# moire_v2_1.net
KiCad netlist of a schematic drawn in EAGLE
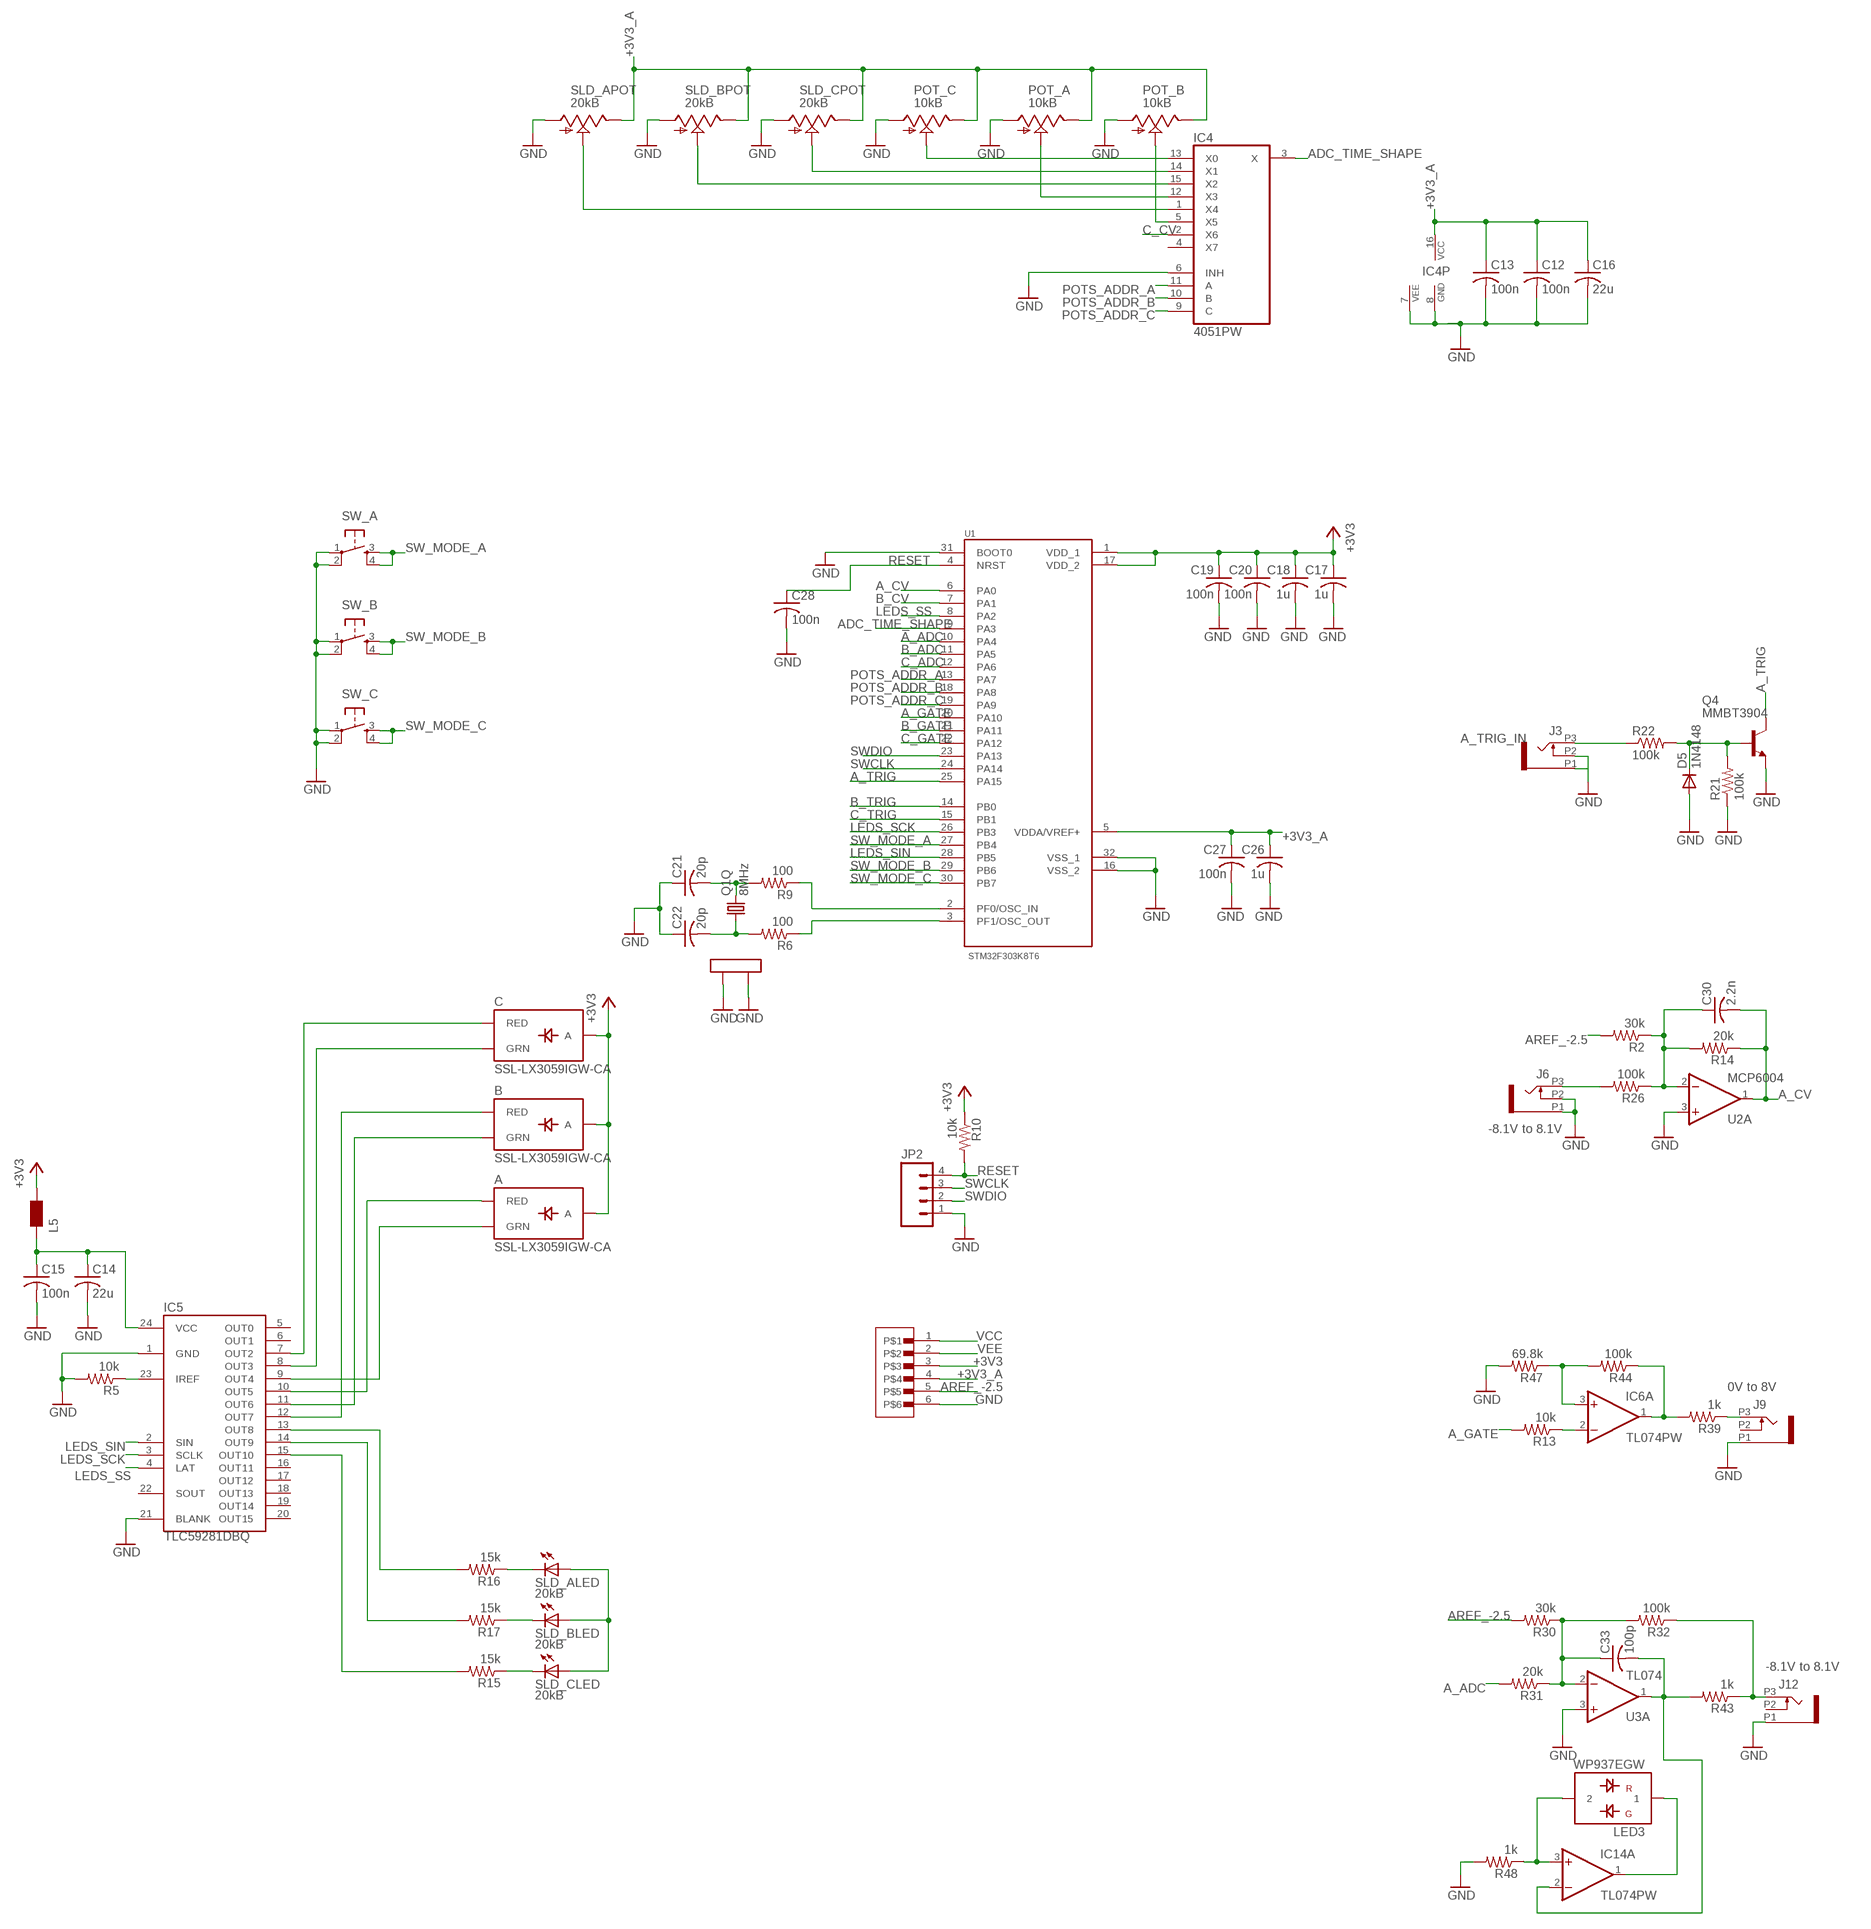
[diagram p0: schematic, sheet 1, part 1 of 2]
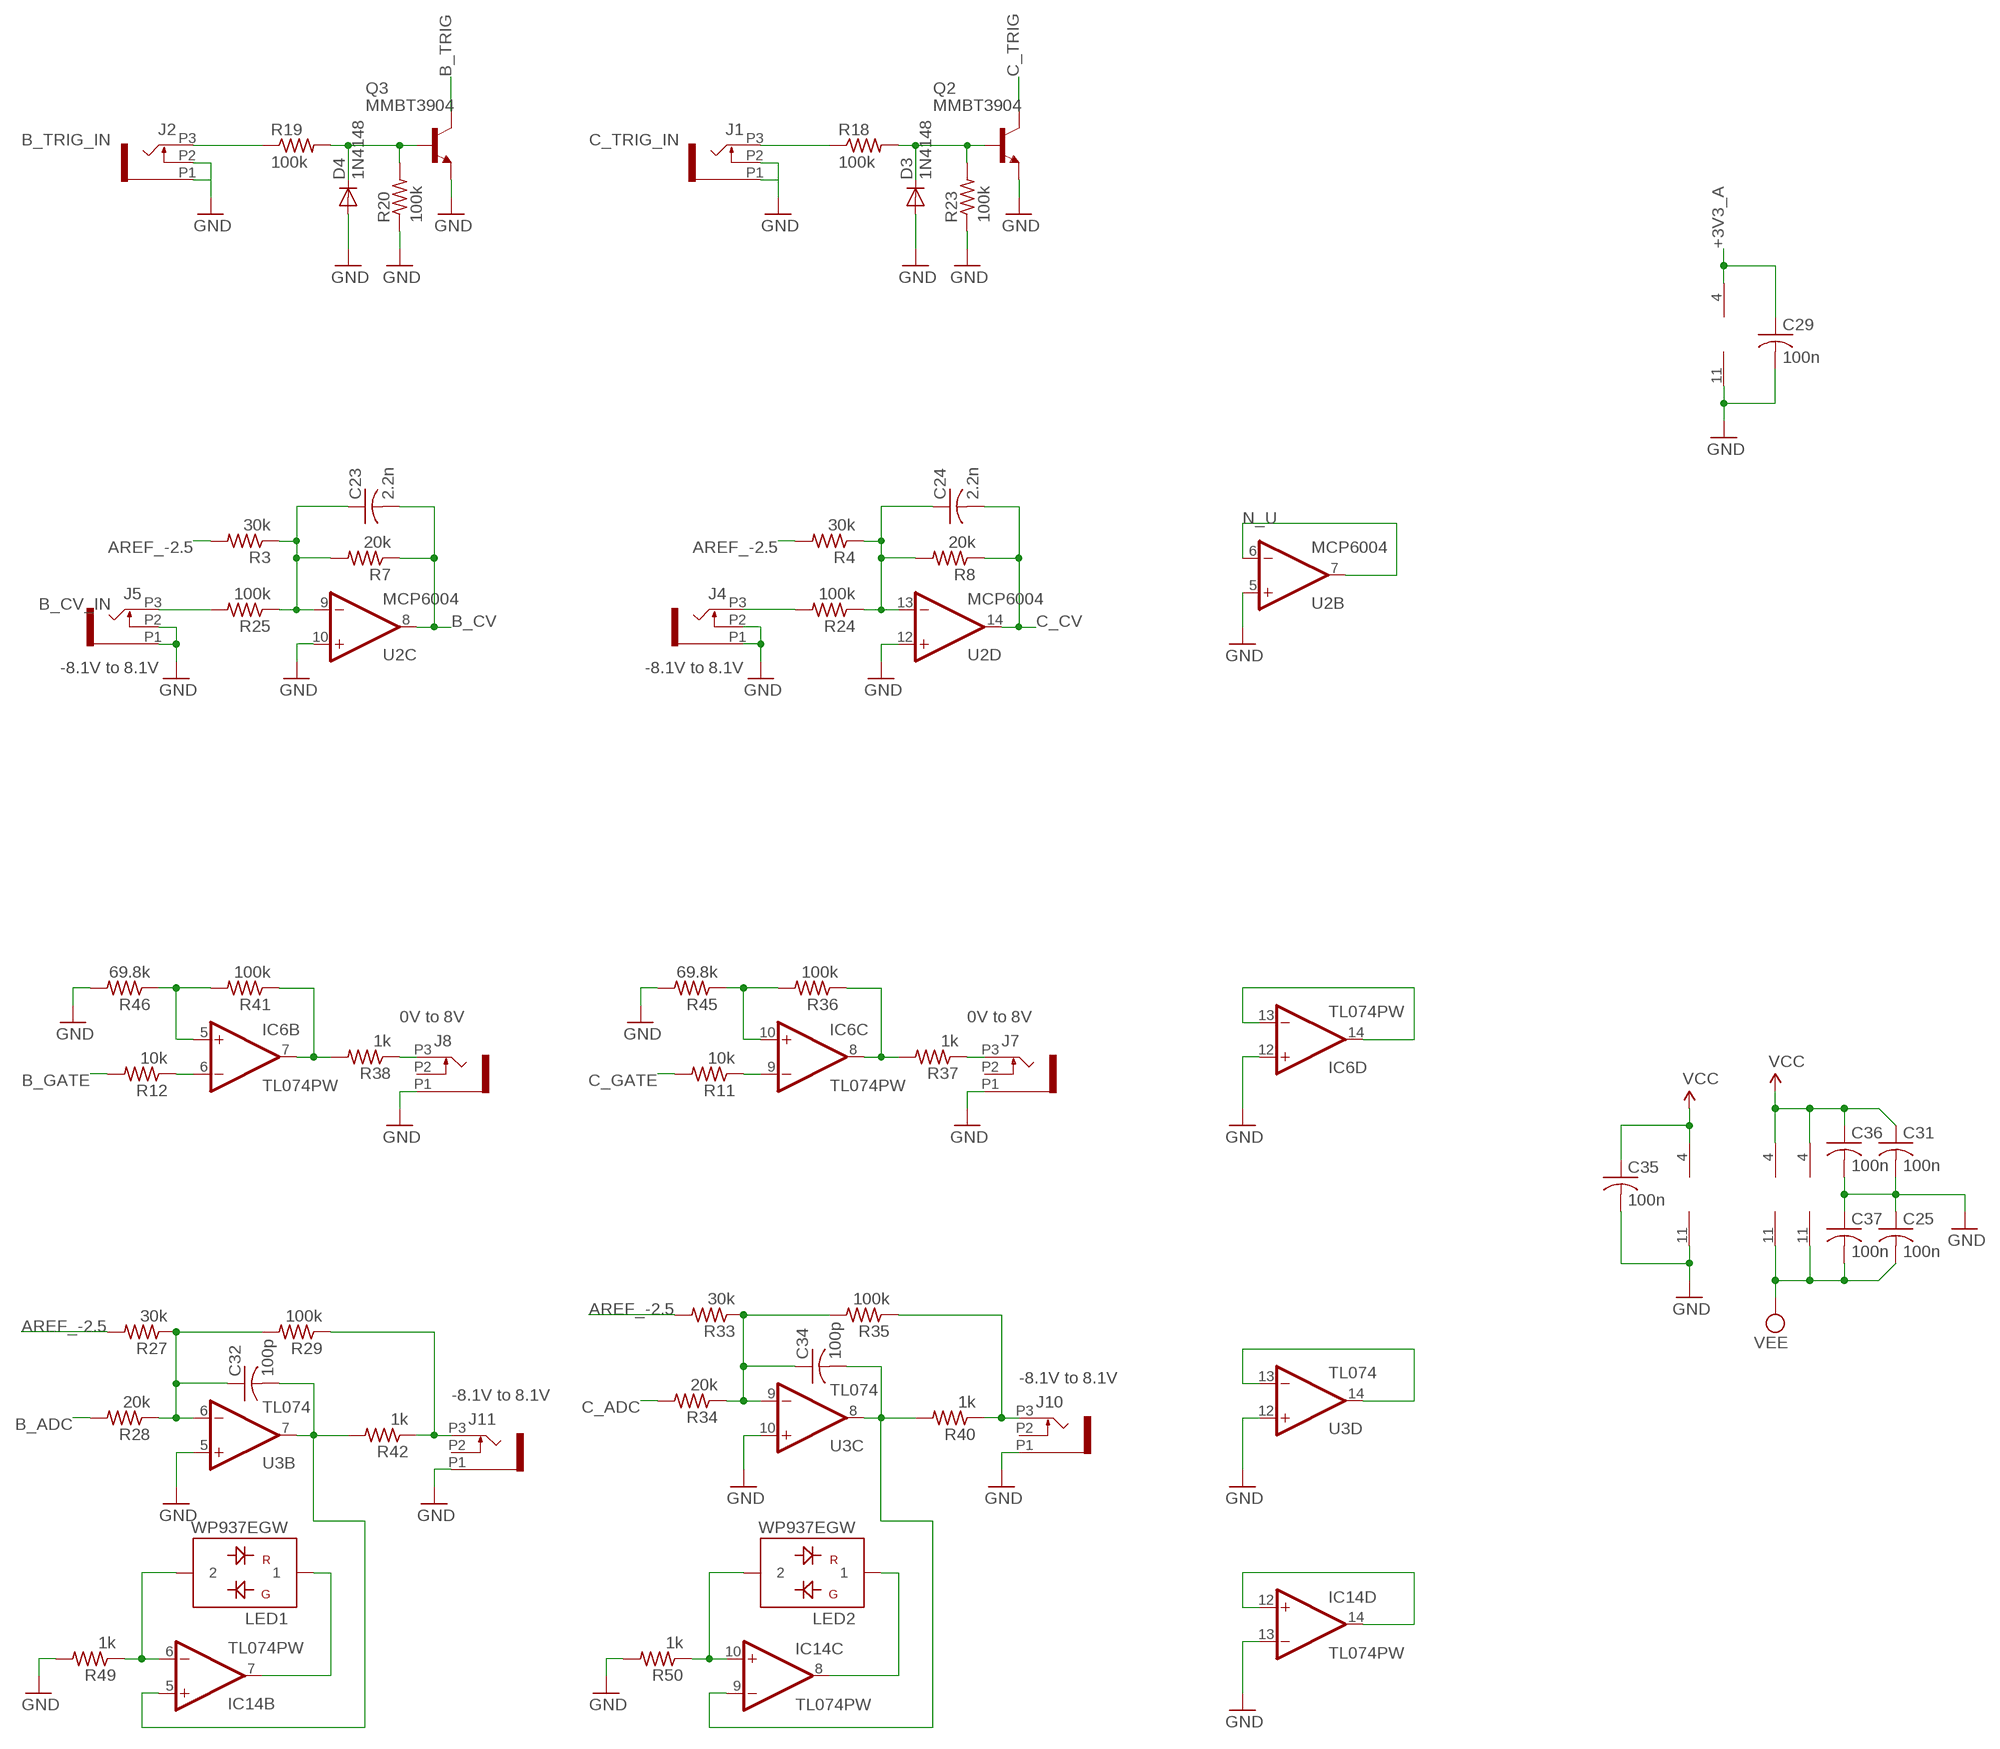
[diagram p1: schematic, sheet 1, part 2 of 2]
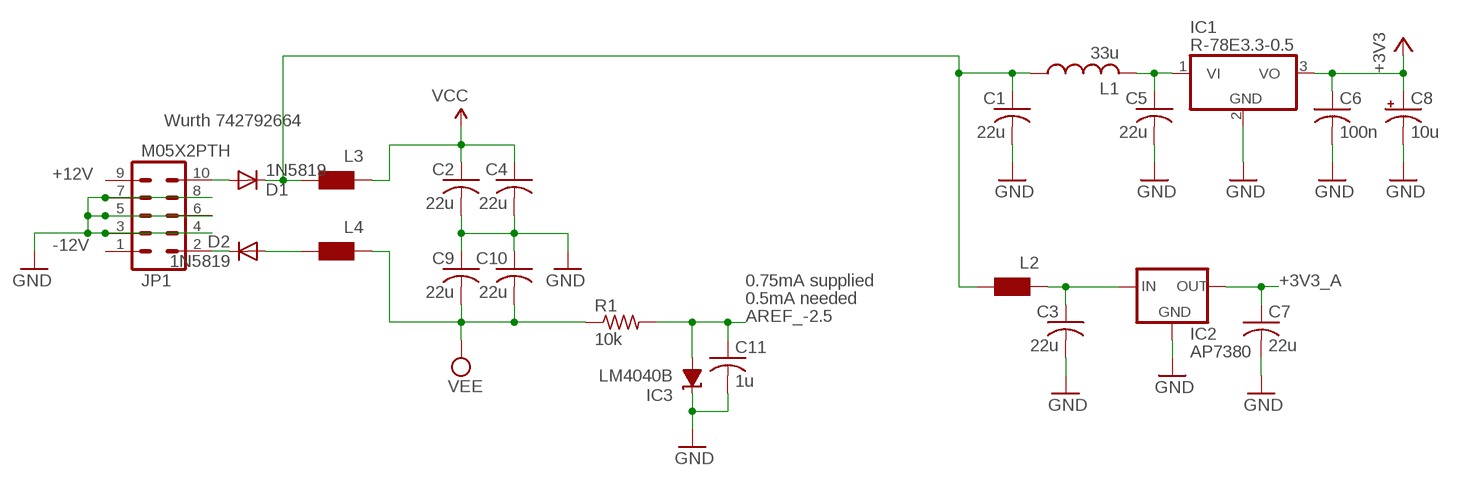
[diagram p2: schematic, sheet 2]

(export (version "E")
  (design (tool "Eeschema 10.0.6"))
  (components
    (comp (ref "C1")
      (value "22u")
      (footprint "eagle-import:RCL_C1206")
      (libsource (lib "eagle-import") (part "RCL_C-USC1206"))
    )
    (comp (ref "C2")
      (value "22u")
      (footprint "eagle-import:RCL_C1206")
      (libsource (lib "eagle-import") (part "RCL_C-USC1206"))
    )
    (comp (ref "C3")
      (value "22u")
      (footprint "eagle-import:RCL_C1206")
      (libsource (lib "eagle-import") (part "RCL_C-USC1206"))
    )
    (comp (ref "C4")
      (value "22u")
      (footprint "eagle-import:RCL_C1206")
      (libsource (lib "eagle-import") (part "RCL_C-USC1206"))
    )
    (comp (ref "C5")
      (value "22u")
      (footprint "eagle-import:RCL_C1206")
      (libsource (lib "eagle-import") (part "RCL_C-USC1206"))
    )
    (comp (ref "C6")
      (value "100n")
      (footprint "eagle-import:RCL_C0603")
      (libsource (lib "eagle-import") (part "RCL_C-USC0603"))
    )
    (comp (ref "C7")
      (value "22u")
      (footprint "eagle-import:RCL_C1206")
      (libsource (lib "eagle-import") (part "RCL_C-USC1206"))
    )
    (comp (ref "C8")
      (value "10u")
      (footprint "eagle-import:RCL_PANASONIC_A")
      (libsource (lib "eagle-import") (part "RCL_CPOL-USA"))
    )
    (comp (ref "C9")
      (value "22u")
      (footprint "eagle-import:RCL_C1206")
      (libsource (lib "eagle-import") (part "RCL_C-USC1206"))
    )
    (comp (ref "C10")
      (value "22u")
      (footprint "eagle-import:RCL_C1206")
      (libsource (lib "eagle-import") (part "RCL_C-USC1206"))
    )
    (comp (ref "C11")
      (value "1u")
      (footprint "eagle-import:RCL_C0603")
      (libsource (lib "eagle-import") (part "RCL_C-USC0603"))
    )
    (comp (ref "D1")
      (value "1N5819")
      (footprint "eagle-import:DIODE_SOD123")
      (libsource (lib "eagle-import") (part "DIODE_DIODE-SOD123"))
    )
    (comp (ref "D2")
      (value "1N5819")
      (footprint "eagle-import:DIODE_SOD123")
      (libsource (lib "eagle-import") (part "DIODE_DIODE-SOD123"))
    )
    (comp (ref "IC1")
      (value "R-78E3.3-0.5")
      (footprint "eagle-import:WE78")
      (libsource (lib "eagle-import") (part "WE173950378"))
    )
    (comp (ref "IC2")
      (value "AP7380")
      (footprint "eagle-import:SOT89")
      (libsource (lib "eagle-import") (part "AP7380"))
    )
    (comp (ref "IC3")
      (value "LM4040B")
      (footprint "eagle-import:DBZ_R-PDSO-G3")
      (libsource (lib "eagle-import") (part "LM4041DBZB12"))
    )
    (comp (ref "JP1")
      (value "M05X2PTH")
      (footprint "eagle-import:2X5-PTH")
      (libsource (lib "eagle-import") (part "M05X2PTH"))
    )
    (comp (ref "L1")
      (value "33u")
      (footprint "eagle-import:L2012C")
      (libsource (lib "eagle-import") (part "L-USL2012C"))
    )
    (comp (ref "L2")
      (value "WE-CBF_0603")
      (footprint "eagle-import:0603")
      (libsource (lib "eagle-import") (part "WE-CBF_0603"))
    )
    (comp (ref "L3")
      (value "WE-CBF_0603")
      (footprint "eagle-import:0603")
      (libsource (lib "eagle-import") (part "WE-CBF_0603"))
    )
    (comp (ref "L4")
      (value "WE-CBF_0603")
      (footprint "eagle-import:0603")
      (libsource (lib "eagle-import") (part "WE-CBF_0603"))
    )
    (comp (ref "R1")
      (value "10k")
      (footprint "eagle-import:RCL_R0603")
      (libsource (lib "eagle-import") (part "RCL_R-US_R0603"))
    )
    (comp (ref "A")
      (value "SSL-LX3059IGW-CA")
      (footprint "eagle-import:LED-BICOLOR-THROUGHHOLE-LUMEX")
      (libsource (lib "eagle-import") (part "LED-BICOLOR-THROUGHHOLE-CA"))
    )
    (comp (ref "B")
      (value "SSL-LX3059IGW-CA")
      (footprint "eagle-import:LED-BICOLOR-THROUGHHOLE-LUMEX")
      (libsource (lib "eagle-import") (part "LED-BICOLOR-THROUGHHOLE-CA"))
    )
    (comp (ref "C")
      (value "SSL-LX3059IGW-CA")
      (footprint "eagle-import:LED-BICOLOR-THROUGHHOLE-LUMEX")
      (libsource (lib "eagle-import") (part "LED-BICOLOR-THROUGHHOLE-CA"))
    )
    (comp (ref "C12")
      (value "100n")
      (footprint "eagle-import:RCL_C0603")
      (libsource (lib "eagle-import") (part "RCL_C-USC0603"))
    )
    (comp (ref "C13")
      (value "100n")
      (footprint "eagle-import:RCL_C0603")
      (libsource (lib "eagle-import") (part "RCL_C-USC0603"))
    )
    (comp (ref "C14")
      (value "22u")
      (footprint "eagle-import:RCL_C1206")
      (libsource (lib "eagle-import") (part "RCL_C-USC1206"))
    )
    (comp (ref "C15")
      (value "100n")
      (footprint "eagle-import:RCL_C0603")
      (libsource (lib "eagle-import") (part "RCL_C-USC0603"))
    )
    (comp (ref "C16")
      (value "22u")
      (footprint "eagle-import:RCL_C1206")
      (libsource (lib "eagle-import") (part "RCL_C-USC1206"))
    )
    (comp (ref "C17")
      (value "1u")
      (footprint "eagle-import:RCL_C0603")
      (libsource (lib "eagle-import") (part "RCL_C-USC0603"))
    )
    (comp (ref "C18")
      (value "1u")
      (footprint "eagle-import:RCL_C0603")
      (libsource (lib "eagle-import") (part "RCL_C-USC0603"))
    )
    (comp (ref "C19")
      (value "100n")
      (footprint "eagle-import:RCL_C0603")
      (libsource (lib "eagle-import") (part "RCL_C-USC0603"))
    )
    (comp (ref "C20")
      (value "100n")
      (footprint "eagle-import:RCL_C0603")
      (libsource (lib "eagle-import") (part "RCL_C-USC0603"))
    )
    (comp (ref "C21")
      (value "20p")
      (footprint "eagle-import:RCL_C0603")
      (libsource (lib "eagle-import") (part "RCL_C-USC0603"))
    )
    (comp (ref "C22")
      (value "20p")
      (footprint "eagle-import:RCL_C0603")
      (libsource (lib "eagle-import") (part "RCL_C-USC0603"))
    )
    (comp (ref "C23")
      (value "2.2n")
      (footprint "eagle-import:RCL_C0603")
      (libsource (lib "eagle-import") (part "RCL_C-USC0603"))
    )
    (comp (ref "C24")
      (value "2.2n")
      (footprint "eagle-import:RCL_C0603")
      (libsource (lib "eagle-import") (part "RCL_C-USC0603"))
    )
    (comp (ref "C25")
      (value "100n")
      (footprint "eagle-import:RCL_C0603")
      (libsource (lib "eagle-import") (part "RCL_C-USC0603"))
    )
    (comp (ref "C26")
      (value "1u")
      (footprint "eagle-import:RCL_C0603")
      (libsource (lib "eagle-import") (part "RCL_C-USC0603"))
    )
    (comp (ref "C27")
      (value "100n")
      (footprint "eagle-import:RCL_C0603")
      (libsource (lib "eagle-import") (part "RCL_C-USC0603"))
    )
    (comp (ref "C28")
      (value "100n")
      (footprint "eagle-import:RCL_C0603")
      (libsource (lib "eagle-import") (part "RCL_C-USC0603"))
    )
    (comp (ref "C29")
      (value "100n")
      (footprint "eagle-import:RCL_C0603")
      (libsource (lib "eagle-import") (part "RCL_C-USC0603"))
    )
    (comp (ref "C30")
      (value "2.2n")
      (footprint "eagle-import:RCL_C0603")
      (libsource (lib "eagle-import") (part "RCL_C-USC0603"))
    )
    (comp (ref "C31")
      (value "100n")
      (footprint "eagle-import:RCL_C0603")
      (libsource (lib "eagle-import") (part "RCL_C-USC0603"))
    )
    (comp (ref "C32")
      (value "100p")
      (footprint "eagle-import:RCL_C0603")
      (libsource (lib "eagle-import") (part "RCL_C-USC0603"))
    )
    (comp (ref "C33")
      (value "100p")
      (footprint "eagle-import:RCL_C0603")
      (libsource (lib "eagle-import") (part "RCL_C-USC0603"))
    )
    (comp (ref "C34")
      (value "100p")
      (footprint "eagle-import:RCL_C0603")
      (libsource (lib "eagle-import") (part "RCL_C-USC0603"))
    )
    (comp (ref "C35")
      (value "100n")
      (footprint "eagle-import:RCL_C0603")
      (libsource (lib "eagle-import") (part "RCL_C-USC0603"))
    )
    (comp (ref "C36")
      (value "100n")
      (footprint "eagle-import:RCL_C0603")
      (libsource (lib "eagle-import") (part "RCL_C-USC0603"))
    )
    (comp (ref "C37")
      (value "100n")
      (footprint "eagle-import:RCL_C0603")
      (libsource (lib "eagle-import") (part "RCL_C-USC0603"))
    )
    (comp (ref "D3")
      (value "1N4148")
      (footprint "eagle-import:DIODE_SOD523")
      (libsource (lib "eagle-import") (part "DIODE_DIODE-SOD523"))
    )
    (comp (ref "D4")
      (value "1N4148")
      (footprint "eagle-import:DIODE_SOD523")
      (libsource (lib "eagle-import") (part "DIODE_DIODE-SOD523"))
    )
    (comp (ref "D5")
      (value "1N4148")
      (footprint "eagle-import:DIODE_SOD523")
      (libsource (lib "eagle-import") (part "DIODE_DIODE-SOD523"))
    )
    (comp (ref "IC4")
      (value "4051PW")
      (footprint "eagle-import:TSSOP16_065")
      (libsource (lib "eagle-import") (part "4051PW"))
    )
    (comp (ref "IC5")
      (value "TLC59281DBQ")
      (footprint "eagle-import:TSSOP24_0635")
      (libsource (lib "eagle-import") (part "TLC59281DBQ"))
    )
    (comp (ref "IC6")
      (value "TL074PW")
      (footprint "eagle-import:TSSOP14_065")
      (libsource (lib "eagle-import") (part "og-linear_TL074PW"))
    )
    (comp (ref "IC14")
      (value "TL074PW")
      (footprint "eagle-import:TSSOP14_065")
      (libsource (lib "eagle-import") (part "TL074PW"))
    )
    (comp (ref "J1")
      (value "PJ301_THONKICONN6")
      (footprint "eagle-import:WQP_PJ_301M6")
      (libsource (lib "eagle-import") (part "PJ301_THONKICONN6"))
    )
    (comp (ref "J2")
      (value "PJ301_THONKICONN6")
      (footprint "eagle-import:WQP_PJ_301M6")
      (libsource (lib "eagle-import") (part "PJ301_THONKICONN6"))
    )
    (comp (ref "J3")
      (value "PJ301_THONKICONN6")
      (footprint "eagle-import:WQP_PJ_301M6")
      (libsource (lib "eagle-import") (part "PJ301_THONKICONN6"))
    )
    (comp (ref "J4")
      (value "PJ301_THONKICONN6")
      (footprint "eagle-import:WQP_PJ_301M6")
      (libsource (lib "eagle-import") (part "PJ301_THONKICONN6"))
    )
    (comp (ref "J5")
      (value "PJ301_THONKICONN6")
      (footprint "eagle-import:WQP_PJ_301M6")
      (libsource (lib "eagle-import") (part "PJ301_THONKICONN6"))
    )
    (comp (ref "J6")
      (value "PJ301_THONKICONN6")
      (footprint "eagle-import:WQP_PJ_301M6")
      (libsource (lib "eagle-import") (part "PJ301_THONKICONN6"))
    )
    (comp (ref "J7")
      (value "PJ301_THONKICONN6")
      (footprint "eagle-import:WQP_PJ_301M6")
      (libsource (lib "eagle-import") (part "PJ301_THONKICONN6"))
    )
    (comp (ref "J8")
      (value "PJ301_THONKICONN6")
      (footprint "eagle-import:WQP_PJ_301M6")
      (libsource (lib "eagle-import") (part "PJ301_THONKICONN6"))
    )
    (comp (ref "J9")
      (value "PJ301_THONKICONN6")
      (footprint "eagle-import:WQP_PJ_301M6")
      (libsource (lib "eagle-import") (part "PJ301_THONKICONN6"))
    )
    (comp (ref "J10")
      (value "PJ301_THONKICONN6")
      (footprint "eagle-import:WQP_PJ_301M6")
      (libsource (lib "eagle-import") (part "PJ301_THONKICONN6"))
    )
    (comp (ref "J11")
      (value "PJ301_THONKICONN6")
      (footprint "eagle-import:WQP_PJ_301M6")
      (libsource (lib "eagle-import") (part "PJ301_THONKICONN6"))
    )
    (comp (ref "J12")
      (value "PJ301_THONKICONN6")
      (footprint "eagle-import:WQP_PJ_301M6")
      (libsource (lib "eagle-import") (part "PJ301_THONKICONN6"))
    )
    (comp (ref "JP2")
      (value "M04PTH")
      (footprint "eagle-import:1X04")
      (libsource (lib "eagle-import") (part "M04PTH"))
    )
    (comp (ref "L5")
      (value "WE-CBF_0603")
      (footprint "eagle-import:0603")
      (libsource (lib "eagle-import") (part "WE-CBF_0603"))
    )
    (comp (ref "LED1")
      (value "WP937EGW")
      (footprint "eagle-import:LED3MM")
      (libsource (lib "eagle-import") (part "LED-BICOLOR-SHARED-THROUGHHOLE"))
    )
    (comp (ref "LED2")
      (value "WP937EGW")
      (footprint "eagle-import:LED3MM")
      (libsource (lib "eagle-import") (part "LED-BICOLOR-SHARED-THROUGHHOLE"))
    )
    (comp (ref "LED3")
      (value "WP937EGW")
      (footprint "eagle-import:LED3MM")
      (libsource (lib "eagle-import") (part "LED-BICOLOR-SHARED-THROUGHHOLE"))
    )
    (comp (ref "POT_A")
      (value "10kB")
      (footprint "eagle-import:ALPS_POT_VERTICAL")
      (libsource (lib "eagle-import") (part "POT_USVERTICAL"))
    )
    (comp (ref "POT_B")
      (value "10kB")
      (footprint "eagle-import:ALPS_POT_VERTICAL")
      (libsource (lib "eagle-import") (part "POT_USVERTICAL"))
    )
    (comp (ref "POT_C")
      (value "10kB")
      (footprint "eagle-import:ALPS_POT_VERTICAL")
      (libsource (lib "eagle-import") (part "POT_USVERTICAL"))
    )
    (comp (ref "Q1")
      (value "8MHz")
      (footprint "eagle-import:CTS406")
      (libsource (lib "eagle-import") (part "CRYSTAL"))
    )
    (comp (ref "Q2")
      (value "MMBT3904")
      (footprint "eagle-import:SOT23-BEC")
      (libsource (lib "eagle-import") (part "-NPN-SOT23-BECMMBT3904LT1"))
    )
    (comp (ref "Q3")
      (value "MMBT3904")
      (footprint "eagle-import:SOT23-BEC")
      (libsource (lib "eagle-import") (part "-NPN-SOT23-BECMMBT3904LT1"))
    )
    (comp (ref "Q4")
      (value "MMBT3904")
      (footprint "eagle-import:SOT23-BEC")
      (libsource (lib "eagle-import") (part "-NPN-SOT23-BECMMBT3904LT1"))
    )
    (comp (ref "R2")
      (value "30k")
      (footprint "eagle-import:RCL_R0603")
      (libsource (lib "eagle-import") (part "RCL_R-US_R0603"))
    )
    (comp (ref "R3")
      (value "30k")
      (footprint "eagle-import:RCL_R0603")
      (libsource (lib "eagle-import") (part "RCL_R-US_R0603"))
    )
    (comp (ref "R4")
      (value "30k")
      (footprint "eagle-import:RCL_R0603")
      (libsource (lib "eagle-import") (part "RCL_R-US_R0603"))
    )
    (comp (ref "R5")
      (value "10k")
      (footprint "eagle-import:RCL_R0603")
      (libsource (lib "eagle-import") (part "RCL_R-US_R0603"))
    )
    (comp (ref "R6")
      (value "100")
      (footprint "eagle-import:RCL_R0603")
      (libsource (lib "eagle-import") (part "RCL_R-US_R0603"))
    )
    (comp (ref "R7")
      (value "20k")
      (footprint "eagle-import:RCL_R0603")
      (libsource (lib "eagle-import") (part "RCL_R-US_R0603"))
    )
    (comp (ref "R8")
      (value "20k")
      (footprint "eagle-import:RCL_R0603")
      (libsource (lib "eagle-import") (part "RCL_R-US_R0603"))
    )
    (comp (ref "R9")
      (value "100")
      (footprint "eagle-import:RCL_R0603")
      (libsource (lib "eagle-import") (part "RCL_R-US_R0603"))
    )
    (comp (ref "R10")
      (value "10k")
      (footprint "eagle-import:RCL_R0603")
      (libsource (lib "eagle-import") (part "RCL_R-US_R0603"))
    )
    (comp (ref "R11")
      (value "10k")
      (footprint "eagle-import:RCL_R0603")
      (libsource (lib "eagle-import") (part "RCL_R-US_R0603"))
    )
    (comp (ref "R12")
      (value "10k")
      (footprint "eagle-import:RCL_R0603")
      (libsource (lib "eagle-import") (part "RCL_R-US_R0603"))
    )
    (comp (ref "R13")
      (value "10k")
      (footprint "eagle-import:RCL_R0603")
      (libsource (lib "eagle-import") (part "RCL_R-US_R0603"))
    )
    (comp (ref "R14")
      (value "20k")
      (footprint "eagle-import:RCL_R0603")
      (libsource (lib "eagle-import") (part "RCL_R-US_R0603"))
    )
    (comp (ref "R15")
      (value "15k")
      (footprint "eagle-import:RCL_R0603")
      (libsource (lib "eagle-import") (part "RCL_R-US_R0603"))
    )
    (comp (ref "R16")
      (value "15k")
      (footprint "eagle-import:RCL_R0603")
      (libsource (lib "eagle-import") (part "RCL_R-US_R0603"))
    )
    (comp (ref "R17")
      (value "15k")
      (footprint "eagle-import:RCL_R0603")
      (libsource (lib "eagle-import") (part "RCL_R-US_R0603"))
    )
    (comp (ref "R18")
      (value "100k")
      (footprint "eagle-import:RCL_R0603")
      (libsource (lib "eagle-import") (part "RCL_R-US_R0603"))
    )
    (comp (ref "R19")
      (value "100k")
      (footprint "eagle-import:RCL_R0603")
      (libsource (lib "eagle-import") (part "RCL_R-US_R0603"))
    )
    (comp (ref "R20")
      (value "100k")
      (footprint "eagle-import:RCL_R0603")
      (libsource (lib "eagle-import") (part "RCL_R-US_R0603"))
    )
    (comp (ref "R21")
      (value "100k")
      (footprint "eagle-import:RCL_R0603")
      (libsource (lib "eagle-import") (part "RCL_R-US_R0603"))
    )
    (comp (ref "R22")
      (value "100k")
      (footprint "eagle-import:RCL_R0603")
      (libsource (lib "eagle-import") (part "RCL_R-US_R0603"))
    )
    (comp (ref "R23")
      (value "100k")
      (footprint "eagle-import:RCL_R0603")
      (libsource (lib "eagle-import") (part "RCL_R-US_R0603"))
    )
    (comp (ref "R24")
      (value "100k")
      (footprint "eagle-import:RCL_R0603")
      (libsource (lib "eagle-import") (part "RCL_R-US_R0603"))
    )
    (comp (ref "R25")
      (value "100k")
      (footprint "eagle-import:RCL_R0603")
      (libsource (lib "eagle-import") (part "RCL_R-US_R0603"))
    )
    (comp (ref "R26")
      (value "100k")
      (footprint "eagle-import:RCL_R0603")
      (libsource (lib "eagle-import") (part "RCL_R-US_R0603"))
    )
    (comp (ref "R27")
      (value "30k")
      (footprint "eagle-import:RCL_R0603")
      (libsource (lib "eagle-import") (part "RCL_R-US_R0603"))
    )
    (comp (ref "R28")
      (value "20k")
      (footprint "eagle-import:RCL_R0603")
      (libsource (lib "eagle-import") (part "RCL_R-US_R0603"))
    )
    (comp (ref "R29")
      (value "100k")
      (footprint "eagle-import:RCL_R0603")
      (libsource (lib "eagle-import") (part "RCL_R-US_R0603"))
    )
    (comp (ref "R30")
      (value "30k")
      (footprint "eagle-import:RCL_R0603")
      (libsource (lib "eagle-import") (part "RCL_R-US_R0603"))
    )
    (comp (ref "R31")
      (value "20k")
      (footprint "eagle-import:RCL_R0603")
      (libsource (lib "eagle-import") (part "RCL_R-US_R0603"))
    )
    (comp (ref "R32")
      (value "100k")
      (footprint "eagle-import:RCL_R0603")
      (libsource (lib "eagle-import") (part "RCL_R-US_R0603"))
    )
    (comp (ref "R33")
      (value "30k")
      (footprint "eagle-import:RCL_R0603")
      (libsource (lib "eagle-import") (part "RCL_R-US_R0603"))
    )
    (comp (ref "R34")
      (value "20k")
      (footprint "eagle-import:RCL_R0603")
      (libsource (lib "eagle-import") (part "RCL_R-US_R0603"))
    )
    (comp (ref "R35")
      (value "100k")
      (footprint "eagle-import:RCL_R0603")
      (libsource (lib "eagle-import") (part "RCL_R-US_R0603"))
    )
    (comp (ref "R36")
      (value "100k")
      (footprint "eagle-import:RCL_R0603")
      (libsource (lib "eagle-import") (part "RCL_R-US_R0603"))
    )
    (comp (ref "R37")
      (value "1k")
      (footprint "eagle-import:RCL_R0603")
      (libsource (lib "eagle-import") (part "RCL_R-US_R0603"))
    )
    (comp (ref "R38")
      (value "1k")
      (footprint "eagle-import:RCL_R0603")
      (libsource (lib "eagle-import") (part "RCL_R-US_R0603"))
    )
    (comp (ref "R39")
      (value "1k")
      (footprint "eagle-import:RCL_R0603")
      (libsource (lib "eagle-import") (part "RCL_R-US_R0603"))
    )
    (comp (ref "R40")
      (value "1k")
      (footprint "eagle-import:RCL_R0603")
      (libsource (lib "eagle-import") (part "RCL_R-US_R0603"))
    )
    (comp (ref "R41")
      (value "100k")
      (footprint "eagle-import:RCL_R0603")
      (libsource (lib "eagle-import") (part "RCL_R-US_R0603"))
    )
    (comp (ref "R42")
      (value "1k")
      (footprint "eagle-import:RCL_R0603")
      (libsource (lib "eagle-import") (part "RCL_R-US_R0603"))
    )
    (comp (ref "R43")
      (value "1k")
      (footprint "eagle-import:RCL_R0603")
      (libsource (lib "eagle-import") (part "RCL_R-US_R0603"))
    )
    (comp (ref "R44")
      (value "100k")
      (footprint "eagle-import:RCL_R0603")
      (libsource (lib "eagle-import") (part "RCL_R-US_R0603"))
    )
    (comp (ref "R45")
      (value "69.8k")
      (footprint "eagle-import:RCL_R0603")
      (libsource (lib "eagle-import") (part "RCL_R-US_R0603"))
    )
    (comp (ref "R46")
      (value "69.8k")
      (footprint "eagle-import:RCL_R0603")
      (libsource (lib "eagle-import") (part "RCL_R-US_R0603"))
    )
    (comp (ref "R47")
      (value "69.8k")
      (footprint "eagle-import:RCL_R0603")
      (libsource (lib "eagle-import") (part "RCL_R-US_R0603"))
    )
    (comp (ref "R48")
      (value "1k")
      (footprint "eagle-import:RCL_R0603")
      (libsource (lib "eagle-import") (part "RCL_R-US_R0603"))
    )
    (comp (ref "R49")
      (value "1k")
      (footprint "eagle-import:RCL_R0603")
      (libsource (lib "eagle-import") (part "RCL_R-US_R0603"))
    )
    (comp (ref "R50")
      (value "1k")
      (footprint "eagle-import:RCL_R0603")
      (libsource (lib "eagle-import") (part "RCL_R-US_R0603"))
    )
    (comp (ref "SLD_A")
      (value "20kB")
      (footprint "eagle-import:BOURNS_SLIDER")
      (libsource (lib "eagle-import") (part "BOURNS_SLIDER"))
    )
    (comp (ref "SLD_B")
      (value "20kB")
      (footprint "eagle-import:BOURNS_SLIDER")
      (libsource (lib "eagle-import") (part "BOURNS_SLIDER"))
    )
    (comp (ref "SLD_C")
      (value "20kB")
      (footprint "eagle-import:BOURNS_SLIDER")
      (libsource (lib "eagle-import") (part "BOURNS_SLIDER"))
    )
    (comp (ref "SW_A")
      (value "TAC_SWITCHPTH")
      (footprint "eagle-import:TACTILE-PTH")
      (libsource (lib "eagle-import") (part "TAC_SWITCHPTH"))
    )
    (comp (ref "SW_B")
      (value "TAC_SWITCHPTH")
      (footprint "eagle-import:TACTILE-PTH")
      (libsource (lib "eagle-import") (part "TAC_SWITCHPTH"))
    )
    (comp (ref "SW_C")
      (value "TAC_SWITCHPTH")
      (footprint "eagle-import:TACTILE-PTH")
      (libsource (lib "eagle-import") (part "TAC_SWITCHPTH"))
    )
    (comp (ref "U$1")
      (value "1X6-SMD-TESTPAD")
      (footprint "eagle-import:6X1-SMD-TESTPAD")
      (libsource (lib "eagle-import") (part "1X6-SMD-TESTPAD"))
    )
    (comp (ref "U1")
      (value "STM32F303K8T6")
      (footprint "eagle-import:QFP80P900X900X160-32N")
      (fields (field (name "MF") "STMicroelectronics"))
      (libsource (lib "eagle-import") (part "STM32F303K8T6"))
    )
    (comp (ref "U2")
      (value "MCP6004")
      (footprint "eagle-import:SO14")
      (libsource (lib "eagle-import") (part "MCP6004_SMD"))
    )
    (comp (ref "U3")
      (value "TL074")
      (footprint "eagle-import:SO14")
      (libsource (lib "eagle-import") (part "TL074_SMD"))
    )
  )
  (nets
    (net (code "1") (name "+3V3") (class "Default")
      (node (ref "A") (pin "A") (pinfunction "A_A") (pintype "bidirectional"))
      (node (ref "B") (pin "A") (pinfunction "A_A") (pintype "bidirectional"))
      (node (ref "C") (pin "A") (pinfunction "A_A") (pintype "bidirectional"))
      (node (ref "C17") (pin "1") (pinfunction "1_1") (pintype "passive"))
      (node (ref "C18") (pin "1") (pinfunction "1_1") (pintype "passive"))
      (node (ref "C19") (pin "1") (pinfunction "1_1") (pintype "passive"))
      (node (ref "C20") (pin "1") (pinfunction "1_1") (pintype "passive"))
      (node (ref "C6") (pin "1") (pinfunction "1_1") (pintype "passive"))
      (node (ref "C8") (pin "+") (pinfunction "+_+") (pintype "passive"))
      (node (ref "IC1") (pin "3") (pinfunction "VO_3") (pintype "passive"))
      (node (ref "L5") (pin "2") (pinfunction "2_2") (pintype "passive"))
      (node (ref "R10") (pin "1") (pinfunction "1_1") (pintype "passive"))
      (node (ref "U$1") (pin "3") (pinfunction "P$3_3") (pintype "bidirectional"))
      (node (ref "U1") (pin "1") (pinfunction "VDD_1_1") (pintype "power_in"))
      (node (ref "U1") (pin "17") (pinfunction "VDD_2_17") (pintype "power_in"))
    )
    (net (code "2") (name "+3V3_A") (class "Default")
      (node (ref "C12") (pin "1") (pinfunction "1_1") (pintype "passive"))
      (node (ref "C13") (pin "1") (pinfunction "1_1") (pintype "passive"))
      (node (ref "C16") (pin "1") (pinfunction "1_1") (pintype "passive"))
      (node (ref "C26") (pin "1") (pinfunction "1_1") (pintype "passive"))
      (node (ref "C27") (pin "1") (pinfunction "1_1") (pintype "passive"))
      (node (ref "C29") (pin "1") (pinfunction "1_1") (pintype "passive"))
      (node (ref "C7") (pin "1") (pinfunction "1_1") (pintype "passive"))
      (node (ref "IC2") (pin "3") (pinfunction "OUT_3") (pintype "passive"))
      (node (ref "IC4") (pin "16") (pinfunction "VCC_16") (pintype "power_in"))
      (node (ref "POT_A") (pin "P$1") (pinfunction "E_P$1") (pintype "passive"))
      (node (ref "POT_B") (pin "P$1") (pinfunction "E_P$1") (pintype "passive"))
      (node (ref "POT_C") (pin "P$1") (pinfunction "E_P$1") (pintype "passive"))
      (node (ref "SLD_A") (pin "3") (pinfunction "E_3") (pintype "passive"))
      (node (ref "SLD_B") (pin "3") (pinfunction "E_3") (pintype "passive"))
      (node (ref "SLD_C") (pin "3") (pinfunction "E_3") (pintype "passive"))
      (node (ref "U$1") (pin "4") (pinfunction "P$4_4") (pintype "bidirectional"))
      (node (ref "U1") (pin "5") (pinfunction "VDDA/VREF+_5") (pintype "power_in"))
      (node (ref "U2") (pin "4") (pinfunction "V+_4") (pintype "power_in"))
    )
    (net (code "3") (name "+12V") (class "Default")
      (node (ref "D1") (pin "A") (pinfunction "A_A") (pintype "passive"))
      (node (ref "JP1") (pin "10") (pinfunction "10_10") (pintype "passive"))
      (node (ref "JP1") (pin "9") (pinfunction "9_9") (pintype "passive"))
    )
    (net (code "4") (name "-12V") (class "Default")
      (node (ref "D2") (pin "C") (pinfunction "C_C") (pintype "passive"))
      (node (ref "JP1") (pin "1") (pinfunction "1_1") (pintype "passive"))
      (node (ref "JP1") (pin "2") (pinfunction "2_2") (pintype "passive"))
    )
    (net (code "5") (name "ADC_TIME_SHAPE") (class "Default")
      (node (ref "IC4") (pin "3") (pinfunction "X_3") (pintype "bidirectional"))
      (node (ref "U1") (pin "9") (pinfunction "PA3_9") (pintype "bidirectional"))
    )
    (net (code "6") (name "AREF_-2.5") (class "Default")
      (node (ref "C11") (pin "1") (pinfunction "1_1") (pintype "passive"))
      (node (ref "IC3") (pin "2") (pinfunction "A_2") (pintype "passive"))
      (node (ref "R1") (pin "2") (pinfunction "2_2") (pintype "passive"))
      (node (ref "R2") (pin "2") (pinfunction "2_2") (pintype "passive"))
      (node (ref "R27") (pin "2") (pinfunction "2_2") (pintype "passive"))
      (node (ref "R3") (pin "2") (pinfunction "2_2") (pintype "passive"))
      (node (ref "R30") (pin "2") (pinfunction "2_2") (pintype "passive"))
      (node (ref "R33") (pin "2") (pinfunction "2_2") (pintype "passive"))
      (node (ref "R4") (pin "2") (pinfunction "2_2") (pintype "passive"))
      (node (ref "U$1") (pin "5") (pinfunction "P$5_5") (pintype "bidirectional"))
    )
    (net (code "7") (name "A_ADC") (class "Default")
      (node (ref "R31") (pin "2") (pinfunction "2_2") (pintype "passive"))
      (node (ref "U1") (pin "10") (pinfunction "PA4_10") (pintype "bidirectional"))
    )
    (net (code "8") (name "A_CV") (class "Default")
      (node (ref "C30") (pin "2") (pinfunction "2_2") (pintype "passive"))
      (node (ref "R14") (pin "1") (pinfunction "1_1") (pintype "passive"))
      (node (ref "U1") (pin "6") (pinfunction "PA0_6") (pintype "bidirectional"))
      (node (ref "U2") (pin "1") (pinfunction "OUT_1") (pintype "output"))
    )
    (net (code "9") (name "A_GATE") (class "Default")
      (node (ref "R13") (pin "2") (pinfunction "2_2") (pintype "passive"))
      (node (ref "U1") (pin "20") (pinfunction "PA10_20") (pintype "bidirectional"))
    )
    (net (code "10") (name "A_TRIG") (class "Default")
      (node (ref "Q4") (pin "C") (pinfunction "C_C") (pintype "passive"))
      (node (ref "U1") (pin "25") (pinfunction "PA15_25") (pintype "bidirectional"))
    )
    (net (code "11") (name "A_TRIG_IN") (class "Default")
      (node (ref "J3") (pin "P3") (pinfunction "3_P3") (pintype "passive"))
      (node (ref "R22") (pin "1") (pinfunction "1_1") (pintype "passive"))
    )
    (net (code "12") (name "B_ADC") (class "Default")
      (node (ref "R28") (pin "2") (pinfunction "2_2") (pintype "passive"))
      (node (ref "U1") (pin "11") (pinfunction "PA5_11") (pintype "bidirectional"))
    )
    (net (code "13") (name "B_CV") (class "Default")
      (node (ref "C23") (pin "2") (pinfunction "2_2") (pintype "passive"))
      (node (ref "R7") (pin "1") (pinfunction "1_1") (pintype "passive"))
      (node (ref "U1") (pin "7") (pinfunction "PA1_7") (pintype "bidirectional"))
      (node (ref "U2") (pin "8") (pinfunction "OUT_8") (pintype "output"))
    )
    (net (code "14") (name "B_CV_IN") (class "Default")
      (node (ref "J5") (pin "P3") (pinfunction "3_P3") (pintype "passive"))
      (node (ref "R25") (pin "2") (pinfunction "2_2") (pintype "passive"))
    )
    (net (code "15") (name "B_GATE") (class "Default")
      (node (ref "R12") (pin "2") (pinfunction "2_2") (pintype "passive"))
      (node (ref "U1") (pin "21") (pinfunction "PA11_21") (pintype "bidirectional"))
    )
    (net (code "16") (name "B_TRIG") (class "Default")
      (node (ref "Q3") (pin "C") (pinfunction "C_C") (pintype "passive"))
      (node (ref "U1") (pin "14") (pinfunction "PB0_14") (pintype "bidirectional"))
    )
    (net (code "17") (name "B_TRIG_IN") (class "Default")
      (node (ref "J2") (pin "P3") (pinfunction "3_P3") (pintype "passive"))
      (node (ref "R19") (pin "1") (pinfunction "1_1") (pintype "passive"))
    )
    (net (code "18") (name "C_ADC") (class "Default")
      (node (ref "R34") (pin "2") (pinfunction "2_2") (pintype "passive"))
      (node (ref "U1") (pin "12") (pinfunction "PA6_12") (pintype "bidirectional"))
    )
    (net (code "19") (name "C_CV") (class "Default")
      (node (ref "C24") (pin "2") (pinfunction "2_2") (pintype "passive"))
      (node (ref "IC4") (pin "2") (pinfunction "X6_2") (pintype "bidirectional"))
      (node (ref "R8") (pin "1") (pinfunction "1_1") (pintype "passive"))
      (node (ref "U2") (pin "14") (pinfunction "OUT_14") (pintype "output"))
    )
    (net (code "20") (name "C_GATE") (class "Default")
      (node (ref "R11") (pin "2") (pinfunction "2_2") (pintype "passive"))
      (node (ref "U1") (pin "22") (pinfunction "PA12_22") (pintype "bidirectional"))
    )
    (net (code "21") (name "C_TRIG") (class "Default")
      (node (ref "Q2") (pin "C") (pinfunction "C_C") (pintype "passive"))
      (node (ref "U1") (pin "15") (pinfunction "PB1_15") (pintype "bidirectional"))
    )
    (net (code "22") (name "C_TRIG_IN") (class "Default")
      (node (ref "J1") (pin "P3") (pinfunction "3_P3") (pintype "passive"))
      (node (ref "R18") (pin "1") (pinfunction "1_1") (pintype "passive"))
    )
    (net (code "23") (name "GND") (class "Default")
      (node (ref "C1") (pin "2") (pinfunction "2_2") (pintype "passive"))
      (node (ref "C10") (pin "1") (pinfunction "1_1") (pintype "passive"))
      (node (ref "C11") (pin "2") (pinfunction "2_2") (pintype "passive"))
      (node (ref "C12") (pin "2") (pinfunction "2_2") (pintype "passive"))
      (node (ref "C13") (pin "2") (pinfunction "2_2") (pintype "passive"))
      (node (ref "C14") (pin "2") (pinfunction "2_2") (pintype "passive"))
      (node (ref "C15") (pin "2") (pinfunction "2_2") (pintype "passive"))
      (node (ref "C16") (pin "2") (pinfunction "2_2") (pintype "passive"))
      (node (ref "C17") (pin "2") (pinfunction "2_2") (pintype "passive"))
      (node (ref "C18") (pin "2") (pinfunction "2_2") (pintype "passive"))
      (node (ref "C19") (pin "2") (pinfunction "2_2") (pintype "passive"))
      (node (ref "C2") (pin "2") (pinfunction "2_2") (pintype "passive"))
      (node (ref "C20") (pin "2") (pinfunction "2_2") (pintype "passive"))
      (node (ref "C21") (pin "1") (pinfunction "1_1") (pintype "passive"))
      (node (ref "C22") (pin "1") (pinfunction "1_1") (pintype "passive"))
      (node (ref "C25") (pin "1") (pinfunction "1_1") (pintype "passive"))
      (node (ref "C26") (pin "2") (pinfunction "2_2") (pintype "passive"))
      (node (ref "C27") (pin "2") (pinfunction "2_2") (pintype "passive"))
      (node (ref "C28") (pin "2") (pinfunction "2_2") (pintype "passive"))
      (node (ref "C29") (pin "2") (pinfunction "2_2") (pintype "passive"))
      (node (ref "C3") (pin "2") (pinfunction "2_2") (pintype "passive"))
      (node (ref "C31") (pin "2") (pinfunction "2_2") (pintype "passive"))
      (node (ref "C35") (pin "2") (pinfunction "2_2") (pintype "passive"))
      (node (ref "C36") (pin "2") (pinfunction "2_2") (pintype "passive"))
      (node (ref "C37") (pin "1") (pinfunction "1_1") (pintype "passive"))
      (node (ref "C4") (pin "2") (pinfunction "2_2") (pintype "passive"))
      (node (ref "C5") (pin "2") (pinfunction "2_2") (pintype "passive"))
      (node (ref "C6") (pin "2") (pinfunction "2_2") (pintype "passive"))
      (node (ref "C7") (pin "2") (pinfunction "2_2") (pintype "passive"))
      (node (ref "C8") (pin "-") (pinfunction "-_-") (pintype "passive"))
      (node (ref "C9") (pin "1") (pinfunction "1_1") (pintype "passive"))
      (node (ref "D3") (pin "A") (pinfunction "A_A") (pintype "passive"))
      (node (ref "D4") (pin "A") (pinfunction "A_A") (pintype "passive"))
      (node (ref "D5") (pin "A") (pinfunction "A_A") (pintype "passive"))
      (node (ref "IC1") (pin "2") (pinfunction "GND_2") (pintype "passive"))
      (node (ref "IC14") (pin "13") (pinfunction "-IN_13") (pintype "input"))
      (node (ref "IC2") (pin "1") (pinfunction "GND_1") (pintype "input"))
      (node (ref "IC3") (pin "1") (pinfunction "C_1") (pintype "passive"))
      (node (ref "IC4") (pin "6") (pinfunction "INH_6") (pintype "input"))
      (node (ref "IC4") (pin "7") (pinfunction "VEE_7") (pintype "power_in"))
      (node (ref "IC4") (pin "8") (pinfunction "GND_8") (pintype "power_in"))
      (node (ref "IC5") (pin "1") (pinfunction "GND_1") (pintype "bidirectional"))
      (node (ref "IC5") (pin "21") (pinfunction "BLANK_21") (pintype "bidirectional"))
      (node (ref "IC6") (pin "11") (pinfunction "V-_11") (pintype "power_in"))
      (node (ref "IC6") (pin "12") (pinfunction "+IN_12") (pintype "input"))
      (node (ref "J1") (pin "P1") (pinfunction "1_P1") (pintype "passive"))
      (node (ref "J1") (pin "P2") (pinfunction "2_P2") (pintype "passive"))
      (node (ref "J10") (pin "P1") (pinfunction "1_P1") (pintype "passive"))
      (node (ref "J11") (pin "P1") (pinfunction "1_P1") (pintype "passive"))
      (node (ref "J12") (pin "P1") (pinfunction "1_P1") (pintype "passive"))
      (node (ref "J2") (pin "P1") (pinfunction "1_P1") (pintype "passive"))
      (node (ref "J2") (pin "P2") (pinfunction "2_P2") (pintype "passive"))
      (node (ref "J3") (pin "P1") (pinfunction "1_P1") (pintype "passive"))
      (node (ref "J3") (pin "P2") (pinfunction "2_P2") (pintype "passive"))
      (node (ref "J4") (pin "P1") (pinfunction "1_P1") (pintype "passive"))
      (node (ref "J4") (pin "P2") (pinfunction "2_P2") (pintype "passive"))
      (node (ref "J5") (pin "P1") (pinfunction "1_P1") (pintype "passive"))
      (node (ref "J5") (pin "P2") (pinfunction "2_P2") (pintype "passive"))
      (node (ref "J6") (pin "P1") (pinfunction "1_P1") (pintype "passive"))
      (node (ref "J6") (pin "P2") (pinfunction "2_P2") (pintype "passive"))
      (node (ref "J7") (pin "P1") (pinfunction "1_P1") (pintype "passive"))
      (node (ref "J8") (pin "P1") (pinfunction "1_P1") (pintype "passive"))
      (node (ref "J9") (pin "P1") (pinfunction "1_P1") (pintype "passive"))
      (node (ref "JP1") (pin "3") (pinfunction "3_3") (pintype "passive"))
      (node (ref "JP1") (pin "4") (pinfunction "4_4") (pintype "passive"))
      (node (ref "JP1") (pin "5") (pinfunction "5_5") (pintype "passive"))
      (node (ref "JP1") (pin "6") (pinfunction "6_6") (pintype "passive"))
      (node (ref "JP1") (pin "7") (pinfunction "7_7") (pintype "passive"))
      (node (ref "JP1") (pin "8") (pinfunction "8_8") (pintype "passive"))
      (node (ref "JP2") (pin "1") (pinfunction "1_1") (pintype "passive"))
      (node (ref "POT_A") (pin "P$3") (pinfunction "A_P$3") (pintype "passive"))
      (node (ref "POT_B") (pin "P$3") (pinfunction "A_P$3") (pintype "passive"))
      (node (ref "POT_C") (pin "P$3") (pinfunction "A_P$3") (pintype "passive"))
      (node (ref "Q1") (pin "2") (pinfunction "LID1_2") (pintype "power_in"))
      (node (ref "Q1") (pin "4") (pinfunction "LID2_4") (pintype "power_in"))
      (node (ref "Q2") (pin "E") (pinfunction "E_E") (pintype "passive"))
      (node (ref "Q3") (pin "E") (pinfunction "E_E") (pintype "passive"))
      (node (ref "Q4") (pin "E") (pinfunction "E_E") (pintype "passive"))
      (node (ref "R20") (pin "1") (pinfunction "1_1") (pintype "passive"))
      (node (ref "R21") (pin "1") (pinfunction "1_1") (pintype "passive"))
      (node (ref "R23") (pin "1") (pinfunction "1_1") (pintype "passive"))
      (node (ref "R45") (pin "2") (pinfunction "2_2") (pintype "passive"))
      (node (ref "R46") (pin "2") (pinfunction "2_2") (pintype "passive"))
      (node (ref "R47") (pin "2") (pinfunction "2_2") (pintype "passive"))
      (node (ref "R48") (pin "2") (pinfunction "2_2") (pintype "passive"))
      (node (ref "R49") (pin "2") (pinfunction "2_2") (pintype "passive"))
      (node (ref "R5") (pin "2") (pinfunction "2_2") (pintype "passive"))
      (node (ref "R50") (pin "2") (pinfunction "2_2") (pintype "passive"))
      (node (ref "SLD_A") (pin "1") (pinfunction "A_1") (pintype "passive"))
      (node (ref "SLD_B") (pin "1") (pinfunction "A_1") (pintype "passive"))
      (node (ref "SLD_C") (pin "1") (pinfunction "A_1") (pintype "passive"))
      (node (ref "SW_A") (pin "1") (pinfunction "1_1") (pintype "passive"))
      (node (ref "SW_A") (pin "2") (pinfunction "2_2") (pintype "passive"))
      (node (ref "SW_B") (pin "1") (pinfunction "1_1") (pintype "passive"))
      (node (ref "SW_B") (pin "2") (pinfunction "2_2") (pintype "passive"))
      (node (ref "SW_C") (pin "1") (pinfunction "1_1") (pintype "passive"))
      (node (ref "SW_C") (pin "2") (pinfunction "2_2") (pintype "passive"))
      (node (ref "U$1") (pin "6") (pinfunction "P$6_6") (pintype "bidirectional"))
      (node (ref "U1") (pin "16") (pinfunction "VSS_2_16") (pintype "power_in"))
      (node (ref "U1") (pin "31") (pinfunction "BOOT0_31") (pintype "input"))
      (node (ref "U1") (pin "32") (pinfunction "VSS_1_32") (pintype "power_in"))
      (node (ref "U2") (pin "10") (pinfunction "+IN_10") (pintype "input"))
      (node (ref "U2") (pin "11") (pinfunction "V-_11") (pintype "power_in"))
      (node (ref "U2") (pin "12") (pinfunction "+IN_12") (pintype "input"))
      (node (ref "U2") (pin "3") (pinfunction "+IN_3") (pintype "input"))
      (node (ref "U2") (pin "5") (pinfunction "+IN_5") (pintype "input"))
      (node (ref "U3") (pin "10") (pinfunction "+IN_10") (pintype "input"))
      (node (ref "U3") (pin "12") (pinfunction "+IN_12") (pintype "input"))
      (node (ref "U3") (pin "3") (pinfunction "+IN_3") (pintype "input"))
      (node (ref "U3") (pin "5") (pinfunction "+IN_5") (pintype "input"))
    )
    (net (code "24") (name "LEDS_SCK") (class "Default")
      (node (ref "IC5") (pin "3") (pinfunction "SCLK_3") (pintype "bidirectional"))
      (node (ref "U1") (pin "26") (pinfunction "PB3_26") (pintype "bidirectional"))
    )
    (net (code "25") (name "LEDS_SIN") (class "Default")
      (node (ref "IC5") (pin "2") (pinfunction "SIN_2") (pintype "bidirectional"))
      (node (ref "U1") (pin "28") (pinfunction "PB5_28") (pintype "bidirectional"))
    )
    (net (code "26") (name "LEDS_SS") (class "Default")
      (node (ref "IC5") (pin "4") (pinfunction "LAT_4") (pintype "bidirectional"))
      (node (ref "U1") (pin "8") (pinfunction "PA2_8") (pintype "bidirectional"))
    )
    (net (code "27") (name "N_U") (class "Default")
      (node (ref "U2") (pin "6") (pinfunction "-IN_6") (pintype "input"))
      (node (ref "U2") (pin "7") (pinfunction "OUT_7") (pintype "output"))
    )
    (net (code "28") (name "Net-(A-GRN)") (class "Default")
      (node (ref "A") (pin "GREEN_C") (pinfunction "GRN_GREEN_C") (pintype "bidirectional"))
      (node (ref "IC5") (pin "9") (pinfunction "OUT4_9") (pintype "bidirectional"))
    )
    (net (code "29") (name "Net-(A-RED)") (class "Default")
      (node (ref "A") (pin "RED_C") (pinfunction "RED_RED_C") (pintype "bidirectional"))
      (node (ref "IC5") (pin "10") (pinfunction "OUT5_10") (pintype "bidirectional"))
    )
    (net (code "30") (name "Net-(B-GRN)") (class "Default")
      (node (ref "B") (pin "GREEN_C") (pinfunction "GRN_GREEN_C") (pintype "bidirectional"))
      (node (ref "IC5") (pin "11") (pinfunction "OUT6_11") (pintype "bidirectional"))
    )
    (net (code "31") (name "Net-(B-RED)") (class "Default")
      (node (ref "B") (pin "RED_C") (pinfunction "RED_RED_C") (pintype "bidirectional"))
      (node (ref "IC5") (pin "12") (pinfunction "OUT7_12") (pintype "bidirectional"))
    )
    (net (code "32") (name "Net-(C-GRN)") (class "Default")
      (node (ref "C") (pin "GREEN_C") (pinfunction "GRN_GREEN_C") (pintype "bidirectional"))
      (node (ref "IC5") (pin "8") (pinfunction "OUT3_8") (pintype "bidirectional"))
    )
    (net (code "33") (name "Net-(C-RED)") (class "Default")
      (node (ref "C") (pin "RED_C") (pinfunction "RED_RED_C") (pintype "bidirectional"))
      (node (ref "IC5") (pin "7") (pinfunction "OUT2_7") (pintype "bidirectional"))
    )
    (net (code "34") (name "Net-(C1-Pad1)") (class "Default")
      (node (ref "C1") (pin "1") (pinfunction "1_1") (pintype "passive"))
      (node (ref "D1") (pin "C") (pinfunction "C_C") (pintype "passive"))
      (node (ref "L1") (pin "1") (pinfunction "1_1") (pintype "passive"))
      (node (ref "L2") (pin "2") (pinfunction "2_2") (pintype "passive"))
      (node (ref "L3") (pin "2") (pinfunction "2_2") (pintype "passive"))
    )
    (net (code "35") (name "Net-(C3-Pad1)") (class "Default")
      (node (ref "C3") (pin "1") (pinfunction "1_1") (pintype "passive"))
      (node (ref "IC2") (pin "2") (pinfunction "IN_2") (pintype "input"))
      (node (ref "IC2") (pin "4") (pinfunction "IN_4") (pintype "input"))
      (node (ref "L2") (pin "1") (pinfunction "1_1") (pintype "passive"))
    )
    (net (code "36") (name "Net-(C22-Pad2)") (class "Default")
      (node (ref "C22") (pin "2") (pinfunction "2_2") (pintype "passive"))
      (node (ref "Q1") (pin "1") (pinfunction "1_1") (pintype "passive"))
      (node (ref "R6") (pin "2") (pinfunction "2_2") (pintype "passive"))
    )
    (net (code "37") (name "Net-(D2-PadA)") (class "Default")
      (node (ref "D2") (pin "A") (pinfunction "A_A") (pintype "passive"))
      (node (ref "L4") (pin "2") (pinfunction "2_2") (pintype "passive"))
    )
    (net (code "38") (name "Net-(D3-PadC)") (class "Default")
      (node (ref "D3") (pin "C") (pinfunction "C_C") (pintype "passive"))
      (node (ref "Q2") (pin "B") (pinfunction "B_B") (pintype "passive"))
      (node (ref "R18") (pin "2") (pinfunction "2_2") (pintype "passive"))
      (node (ref "R23") (pin "2") (pinfunction "2_2") (pintype "passive"))
    )
    (net (code "39") (name "Net-(D4-PadC)") (class "Default")
      (node (ref "D4") (pin "C") (pinfunction "C_C") (pintype "passive"))
      (node (ref "Q3") (pin "B") (pinfunction "B_B") (pintype "passive"))
      (node (ref "R19") (pin "2") (pinfunction "2_2") (pintype "passive"))
      (node (ref "R20") (pin "2") (pinfunction "2_2") (pintype "passive"))
    )
    (net (code "40") (name "Net-(D5-PadC)") (class "Default")
      (node (ref "D5") (pin "C") (pinfunction "C_C") (pintype "passive"))
      (node (ref "Q4") (pin "B") (pinfunction "B_B") (pintype "passive"))
      (node (ref "R21") (pin "2") (pinfunction "2_2") (pintype "passive"))
      (node (ref "R22") (pin "2") (pinfunction "2_2") (pintype "passive"))
    )
    (net (code "41") (name "Net-(IC1-VI)") (class "Default")
      (node (ref "C5") (pin "1") (pinfunction "1_1") (pintype "passive"))
      (node (ref "IC1") (pin "1") (pinfunction "VI_1") (pintype "input"))
      (node (ref "L1") (pin "2") (pinfunction "2_2") (pintype "passive"))
    )
    (net (code "42") (name "Net-(IC4A-X0)") (class "Default")
      (node (ref "IC4") (pin "13") (pinfunction "X0_13") (pintype "bidirectional"))
      (node (ref "POT_C") (pin "P$2") (pinfunction "S_P$2") (pintype "passive"))
    )
    (net (code "43") (name "Net-(IC4A-X1)") (class "Default")
      (node (ref "IC4") (pin "14") (pinfunction "X1_14") (pintype "bidirectional"))
      (node (ref "SLD_C") (pin "2") (pinfunction "S_2") (pintype "passive"))
    )
    (net (code "44") (name "Net-(IC4A-X2)") (class "Default")
      (node (ref "IC4") (pin "15") (pinfunction "X2_15") (pintype "bidirectional"))
      (node (ref "SLD_B") (pin "2") (pinfunction "S_2") (pintype "passive"))
    )
    (net (code "45") (name "Net-(IC4A-X3)") (class "Default")
      (node (ref "IC4") (pin "12") (pinfunction "X3_12") (pintype "bidirectional"))
      (node (ref "POT_A") (pin "P$2") (pinfunction "S_P$2") (pintype "passive"))
    )
    (net (code "46") (name "Net-(IC4A-X4)") (class "Default")
      (node (ref "IC4") (pin "1") (pinfunction "X4_1") (pintype "bidirectional"))
      (node (ref "SLD_A") (pin "2") (pinfunction "S_2") (pintype "passive"))
    )
    (net (code "47") (name "Net-(IC4A-X5)") (class "Default")
      (node (ref "IC4") (pin "5") (pinfunction "X5_5") (pintype "bidirectional"))
      (node (ref "POT_B") (pin "P$2") (pinfunction "S_P$2") (pintype "passive"))
    )
    (net (code "48") (name "Net-(IC5-IREF)") (class "Default")
      (node (ref "IC5") (pin "23") (pinfunction "IREF_23") (pintype "bidirectional"))
      (node (ref "R5") (pin "1") (pinfunction "1_1") (pintype "passive"))
    )
    (net (code "49") (name "Net-(IC5-OUT8)") (class "Default")
      (node (ref "IC5") (pin "13") (pinfunction "OUT8_13") (pintype "bidirectional"))
      (node (ref "R16") (pin "2") (pinfunction "2_2") (pintype "passive"))
    )
    (net (code "50") (name "Net-(IC5-OUT9)") (class "Default")
      (node (ref "IC5") (pin "14") (pinfunction "OUT9_14") (pintype "bidirectional"))
      (node (ref "R17") (pin "2") (pinfunction "2_2") (pintype "passive"))
    )
    (net (code "51") (name "Net-(IC5-OUT10)") (class "Default")
      (node (ref "IC5") (pin "15") (pinfunction "OUT10_15") (pintype "bidirectional"))
      (node (ref "R15") (pin "2") (pinfunction "2_2") (pintype "passive"))
    )
    (net (code "52") (name "Net-(IC5-VCC)") (class "Default")
      (node (ref "C14") (pin "1") (pinfunction "1_1") (pintype "passive"))
      (node (ref "C15") (pin "1") (pinfunction "1_1") (pintype "passive"))
      (node (ref "IC5") (pin "24") (pinfunction "VCC_24") (pintype "bidirectional"))
      (node (ref "L5") (pin "1") (pinfunction "1_1") (pintype "passive"))
    )
    (net (code "53") (name "Net-(IC6A-+IN)") (class "Default")
      (node (ref "IC6") (pin "3") (pinfunction "+IN_3") (pintype "input"))
      (node (ref "R44") (pin "2") (pinfunction "2_2") (pintype "passive"))
      (node (ref "R47") (pin "1") (pinfunction "1_1") (pintype "passive"))
    )
    (net (code "54") (name "Net-(IC6A--IN)") (class "Default")
      (node (ref "IC6") (pin "2") (pinfunction "-IN_2") (pintype "input"))
      (node (ref "R13") (pin "1") (pinfunction "1_1") (pintype "passive"))
    )
    (net (code "55") (name "Net-(IC6A-OUT)") (class "Default")
      (node (ref "IC6") (pin "1") (pinfunction "OUT_1") (pintype "output"))
      (node (ref "R39") (pin "2") (pinfunction "2_2") (pintype "passive"))
      (node (ref "R44") (pin "1") (pinfunction "1_1") (pintype "passive"))
    )
    (net (code "56") (name "Net-(IC6B-+IN)") (class "Default")
      (node (ref "IC6") (pin "5") (pinfunction "+IN_5") (pintype "input"))
      (node (ref "R41") (pin "2") (pinfunction "2_2") (pintype "passive"))
      (node (ref "R46") (pin "1") (pinfunction "1_1") (pintype "passive"))
    )
    (net (code "57") (name "Net-(IC6B--IN)") (class "Default")
      (node (ref "IC6") (pin "6") (pinfunction "-IN_6") (pintype "input"))
      (node (ref "R12") (pin "1") (pinfunction "1_1") (pintype "passive"))
    )
    (net (code "58") (name "Net-(IC6B-OUT)") (class "Default")
      (node (ref "IC6") (pin "7") (pinfunction "OUT_7") (pintype "output"))
      (node (ref "R38") (pin "2") (pinfunction "2_2") (pintype "passive"))
      (node (ref "R41") (pin "1") (pinfunction "1_1") (pintype "passive"))
    )
    (net (code "59") (name "Net-(IC6C-+IN)") (class "Default")
      (node (ref "IC6") (pin "10") (pinfunction "+IN_10") (pintype "input"))
      (node (ref "R36") (pin "2") (pinfunction "2_2") (pintype "passive"))
      (node (ref "R45") (pin "1") (pinfunction "1_1") (pintype "passive"))
    )
    (net (code "60") (name "Net-(IC6C--IN)") (class "Default")
      (node (ref "IC6") (pin "9") (pinfunction "-IN_9") (pintype "input"))
      (node (ref "R11") (pin "1") (pinfunction "1_1") (pintype "passive"))
    )
    (net (code "61") (name "Net-(IC6C-OUT)") (class "Default")
      (node (ref "IC6") (pin "8") (pinfunction "OUT_8") (pintype "output"))
      (node (ref "R36") (pin "1") (pinfunction "1_1") (pintype "passive"))
      (node (ref "R37") (pin "2") (pinfunction "2_2") (pintype "passive"))
    )
    (net (code "62") (name "Net-(IC6D--IN)") (class "Default")
      (node (ref "IC6") (pin "13") (pinfunction "-IN_13") (pintype "input"))
      (node (ref "IC6") (pin "14") (pinfunction "OUT_14") (pintype "output"))
    )
    (net (code "63") (name "Net-(IC14A-+IN)") (class "Default")
      (node (ref "IC14") (pin "3") (pinfunction "+IN_3") (pintype "input"))
      (node (ref "LED3") (pin "2") (pinfunction "2_2") (pintype "bidirectional"))
      (node (ref "R48") (pin "1") (pinfunction "1_1") (pintype "passive"))
    )
    (net (code "64") (name "Net-(IC14A--IN)") (class "Default")
      (node (ref "C33") (pin "2") (pinfunction "2_2") (pintype "passive"))
      (node (ref "IC14") (pin "2") (pinfunction "-IN_2") (pintype "input"))
      (node (ref "R43") (pin "2") (pinfunction "2_2") (pintype "passive"))
      (node (ref "U3") (pin "1") (pinfunction "OUT_1") (pintype "output"))
    )
    (net (code "65") (name "Net-(IC14A-OUT)") (class "Default")
      (node (ref "IC14") (pin "1") (pinfunction "OUT_1") (pintype "output"))
      (node (ref "LED3") (pin "1") (pinfunction "1_1") (pintype "bidirectional"))
    )
    (net (code "66") (name "Net-(IC14B-+IN)") (class "Default")
      (node (ref "C32") (pin "2") (pinfunction "2_2") (pintype "passive"))
      (node (ref "IC14") (pin "5") (pinfunction "+IN_5") (pintype "input"))
      (node (ref "R42") (pin "2") (pinfunction "2_2") (pintype "passive"))
      (node (ref "U3") (pin "7") (pinfunction "OUT_7") (pintype "output"))
    )
    (net (code "67") (name "Net-(IC14B--IN)") (class "Default")
      (node (ref "IC14") (pin "6") (pinfunction "-IN_6") (pintype "input"))
      (node (ref "LED1") (pin "2") (pinfunction "2_2") (pintype "bidirectional"))
      (node (ref "R49") (pin "1") (pinfunction "1_1") (pintype "passive"))
    )
    (net (code "68") (name "Net-(IC14B-OUT)") (class "Default")
      (node (ref "IC14") (pin "7") (pinfunction "OUT_7") (pintype "output"))
      (node (ref "LED1") (pin "1") (pinfunction "1_1") (pintype "bidirectional"))
    )
    (net (code "69") (name "Net-(IC14C-+IN)") (class "Default")
      (node (ref "IC14") (pin "10") (pinfunction "+IN_10") (pintype "input"))
      (node (ref "LED2") (pin "2") (pinfunction "2_2") (pintype "bidirectional"))
      (node (ref "R50") (pin "1") (pinfunction "1_1") (pintype "passive"))
    )
    (net (code "70") (name "Net-(IC14C--IN)") (class "Default")
      (node (ref "C34") (pin "2") (pinfunction "2_2") (pintype "passive"))
      (node (ref "IC14") (pin "9") (pinfunction "-IN_9") (pintype "input"))
      (node (ref "R40") (pin "2") (pinfunction "2_2") (pintype "passive"))
      (node (ref "U3") (pin "8") (pinfunction "OUT_8") (pintype "output"))
    )
    (net (code "71") (name "Net-(IC14C-OUT)") (class "Default")
      (node (ref "IC14") (pin "8") (pinfunction "OUT_8") (pintype "output"))
      (node (ref "LED2") (pin "1") (pinfunction "1_1") (pintype "bidirectional"))
    )
    (net (code "72") (name "Net-(IC14D-+IN)") (class "Default")
      (node (ref "IC14") (pin "12") (pinfunction "+IN_12") (pintype "input"))
      (node (ref "IC14") (pin "14") (pinfunction "OUT_14") (pintype "output"))
    )
    (net (code "73") (name "Net-(J4-3)") (class "Default")
      (node (ref "J4") (pin "P3") (pinfunction "3_P3") (pintype "passive"))
      (node (ref "R24") (pin "2") (pinfunction "2_2") (pintype "passive"))
    )
    (net (code "74") (name "Net-(J6-3)") (class "Default")
      (node (ref "J6") (pin "P3") (pinfunction "3_P3") (pintype "passive"))
      (node (ref "R26") (pin "2") (pinfunction "2_2") (pintype "passive"))
    )
    (net (code "75") (name "Net-(J7-3)") (class "Default")
      (node (ref "J7") (pin "P3") (pinfunction "3_P3") (pintype "passive"))
      (node (ref "R37") (pin "1") (pinfunction "1_1") (pintype "passive"))
    )
    (net (code "76") (name "Net-(J8-3)") (class "Default")
      (node (ref "J8") (pin "P3") (pinfunction "3_P3") (pintype "passive"))
      (node (ref "R38") (pin "1") (pinfunction "1_1") (pintype "passive"))
    )
    (net (code "77") (name "Net-(J9-3)") (class "Default")
      (node (ref "J9") (pin "P3") (pinfunction "3_P3") (pintype "passive"))
      (node (ref "R39") (pin "1") (pinfunction "1_1") (pintype "passive"))
    )
    (net (code "78") (name "Net-(J10-3)") (class "Default")
      (node (ref "J10") (pin "P3") (pinfunction "3_P3") (pintype "passive"))
      (node (ref "R35") (pin "1") (pinfunction "1_1") (pintype "passive"))
      (node (ref "R40") (pin "1") (pinfunction "1_1") (pintype "passive"))
    )
    (net (code "79") (name "Net-(J11-3)") (class "Default")
      (node (ref "J11") (pin "P3") (pinfunction "3_P3") (pintype "passive"))
      (node (ref "R29") (pin "1") (pinfunction "1_1") (pintype "passive"))
      (node (ref "R42") (pin "1") (pinfunction "1_1") (pintype "passive"))
    )
    (net (code "80") (name "Net-(J12-3)") (class "Default")
      (node (ref "J12") (pin "P3") (pinfunction "3_P3") (pintype "passive"))
      (node (ref "R32") (pin "1") (pinfunction "1_1") (pintype "passive"))
      (node (ref "R43") (pin "1") (pinfunction "1_1") (pintype "passive"))
    )
    (net (code "81") (name "Net-(Q1B-2)") (class "Default")
      (node (ref "C21") (pin "2") (pinfunction "2_2") (pintype "passive"))
      (node (ref "Q1") (pin "3") (pinfunction "2_3") (pintype "passive"))
      (node (ref "R9") (pin "2") (pinfunction "2_2") (pintype "passive"))
    )
    (net (code "82") (name "Net-(SLD_AA-A)") (class "Default")
      (node (ref "SLD_A") (pin "B") (pinfunction "A_B") (pintype "passive"))
      (node (ref "SLD_B") (pin "B") (pinfunction "A_B") (pintype "passive"))
      (node (ref "SLD_C") (pin "B") (pinfunction "A_B") (pintype "passive"))
    )
    (net (code "83") (name "Net-(SLD_AA-C)") (class "Default")
      (node (ref "R16") (pin "1") (pinfunction "1_1") (pintype "passive"))
      (node (ref "SLD_A") (pin "E") (pinfunction "C_E") (pintype "passive"))
    )
    (net (code "84") (name "Net-(SLD_BA-C)") (class "Default")
      (node (ref "R17") (pin "1") (pinfunction "1_1") (pintype "passive"))
      (node (ref "SLD_B") (pin "E") (pinfunction "C_E") (pintype "passive"))
    )
    (net (code "85") (name "Net-(SLD_CA-C)") (class "Default")
      (node (ref "R15") (pin "1") (pinfunction "1_1") (pintype "passive"))
      (node (ref "SLD_C") (pin "E") (pinfunction "C_E") (pintype "passive"))
    )
    (net (code "86") (name "Net-(U1-PF0{slash}OSC_IN)") (class "Default")
      (node (ref "R9") (pin "1") (pinfunction "1_1") (pintype "passive"))
      (node (ref "U1") (pin "2") (pinfunction "PF0/OSC_IN_2") (pintype "bidirectional"))
    )
    (net (code "87") (name "Net-(U1-PF1{slash}OSC_OUT)") (class "Default")
      (node (ref "R6") (pin "1") (pinfunction "1_1") (pintype "passive"))
      (node (ref "U1") (pin "3") (pinfunction "PF1/OSC_OUT_3") (pintype "bidirectional"))
    )
    (net (code "88") (name "Net-(U2A--IN)") (class "Default")
      (node (ref "C30") (pin "1") (pinfunction "1_1") (pintype "passive"))
      (node (ref "R14") (pin "2") (pinfunction "2_2") (pintype "passive"))
      (node (ref "R2") (pin "1") (pinfunction "1_1") (pintype "passive"))
      (node (ref "R26") (pin "1") (pinfunction "1_1") (pintype "passive"))
      (node (ref "U2") (pin "2") (pinfunction "-IN_2") (pintype "input"))
    )
    (net (code "89") (name "Net-(U2C--IN)") (class "Default")
      (node (ref "C23") (pin "1") (pinfunction "1_1") (pintype "passive"))
      (node (ref "R25") (pin "1") (pinfunction "1_1") (pintype "passive"))
      (node (ref "R3") (pin "1") (pinfunction "1_1") (pintype "passive"))
      (node (ref "R7") (pin "2") (pinfunction "2_2") (pintype "passive"))
      (node (ref "U2") (pin "9") (pinfunction "-IN_9") (pintype "input"))
    )
    (net (code "90") (name "Net-(U2D--IN)") (class "Default")
      (node (ref "C24") (pin "1") (pinfunction "1_1") (pintype "passive"))
      (node (ref "R24") (pin "1") (pinfunction "1_1") (pintype "passive"))
      (node (ref "R4") (pin "1") (pinfunction "1_1") (pintype "passive"))
      (node (ref "R8") (pin "2") (pinfunction "2_2") (pintype "passive"))
      (node (ref "U2") (pin "13") (pinfunction "-IN_13") (pintype "input"))
    )
    (net (code "91") (name "Net-(U3A--IN)") (class "Default")
      (node (ref "C33") (pin "1") (pinfunction "1_1") (pintype "passive"))
      (node (ref "R30") (pin "1") (pinfunction "1_1") (pintype "passive"))
      (node (ref "R31") (pin "1") (pinfunction "1_1") (pintype "passive"))
      (node (ref "R32") (pin "2") (pinfunction "2_2") (pintype "passive"))
      (node (ref "U3") (pin "2") (pinfunction "-IN_2") (pintype "input"))
    )
    (net (code "92") (name "Net-(U3B--IN)") (class "Default")
      (node (ref "C32") (pin "1") (pinfunction "1_1") (pintype "passive"))
      (node (ref "R27") (pin "1") (pinfunction "1_1") (pintype "passive"))
      (node (ref "R28") (pin "1") (pinfunction "1_1") (pintype "passive"))
      (node (ref "R29") (pin "2") (pinfunction "2_2") (pintype "passive"))
      (node (ref "U3") (pin "6") (pinfunction "-IN_6") (pintype "input"))
    )
    (net (code "93") (name "Net-(U3C--IN)") (class "Default")
      (node (ref "C34") (pin "1") (pinfunction "1_1") (pintype "passive"))
      (node (ref "R33") (pin "1") (pinfunction "1_1") (pintype "passive"))
      (node (ref "R34") (pin "1") (pinfunction "1_1") (pintype "passive"))
      (node (ref "R35") (pin "2") (pinfunction "2_2") (pintype "passive"))
      (node (ref "U3") (pin "9") (pinfunction "-IN_9") (pintype "input"))
    )
    (net (code "94") (name "Net-(U3D--IN)") (class "Default")
      (node (ref "U3") (pin "13") (pinfunction "-IN_13") (pintype "input"))
      (node (ref "U3") (pin "14") (pinfunction "OUT_14") (pintype "output"))
    )
    (net (code "95") (name "POTS_ADDR_A") (class "Default")
      (node (ref "IC4") (pin "11") (pinfunction "A_11") (pintype "input"))
      (node (ref "U1") (pin "13") (pinfunction "PA7_13") (pintype "bidirectional"))
    )
    (net (code "96") (name "POTS_ADDR_B") (class "Default")
      (node (ref "IC4") (pin "10") (pinfunction "B_10") (pintype "input"))
      (node (ref "U1") (pin "18") (pinfunction "PA8_18") (pintype "bidirectional"))
    )
    (net (code "97") (name "POTS_ADDR_C") (class "Default")
      (node (ref "IC4") (pin "9") (pinfunction "C_9") (pintype "input"))
      (node (ref "U1") (pin "19") (pinfunction "PA9_19") (pintype "bidirectional"))
    )
    (net (code "98") (name "RESET") (class "Default")
      (node (ref "C28") (pin "1") (pinfunction "1_1") (pintype "passive"))
      (node (ref "JP2") (pin "4") (pinfunction "4_4") (pintype "passive"))
      (node (ref "R10") (pin "2") (pinfunction "2_2") (pintype "passive"))
      (node (ref "U1") (pin "4") (pinfunction "NRST_4") (pintype "bidirectional"))
    )
    (net (code "99") (name "SWCLK") (class "Default")
      (node (ref "JP2") (pin "3") (pinfunction "3_3") (pintype "passive"))
      (node (ref "U1") (pin "24") (pinfunction "PA14_24") (pintype "bidirectional"))
    )
    (net (code "100") (name "SWDIO") (class "Default")
      (node (ref "JP2") (pin "2") (pinfunction "2_2") (pintype "passive"))
      (node (ref "U1") (pin "23") (pinfunction "PA13_23") (pintype "bidirectional"))
    )
    (net (code "101") (name "SW_MODE_A") (class "Default")
      (node (ref "SW_A") (pin "3") (pinfunction "3_3") (pintype "passive"))
      (node (ref "SW_A") (pin "4") (pinfunction "4_4") (pintype "passive"))
      (node (ref "U1") (pin "27") (pinfunction "PB4_27") (pintype "bidirectional"))
    )
    (net (code "102") (name "SW_MODE_B") (class "Default")
      (node (ref "SW_B") (pin "3") (pinfunction "3_3") (pintype "passive"))
      (node (ref "SW_B") (pin "4") (pinfunction "4_4") (pintype "passive"))
      (node (ref "U1") (pin "29") (pinfunction "PB6_29") (pintype "bidirectional"))
    )
    (net (code "103") (name "SW_MODE_C") (class "Default")
      (node (ref "SW_C") (pin "3") (pinfunction "3_3") (pintype "passive"))
      (node (ref "SW_C") (pin "4") (pinfunction "4_4") (pintype "passive"))
      (node (ref "U1") (pin "30") (pinfunction "PB7_30") (pintype "bidirectional"))
    )
    (net (code "104") (name "VCC") (class "Default")
      (node (ref "C2") (pin "1") (pinfunction "1_1") (pintype "passive"))
      (node (ref "C31") (pin "1") (pinfunction "1_1") (pintype "passive"))
      (node (ref "C35") (pin "1") (pinfunction "1_1") (pintype "passive"))
      (node (ref "C36") (pin "1") (pinfunction "1_1") (pintype "passive"))
      (node (ref "C4") (pin "1") (pinfunction "1_1") (pintype "passive"))
      (node (ref "IC14") (pin "4") (pinfunction "V+_4") (pintype "power_in"))
      (node (ref "IC6") (pin "4") (pinfunction "V+_4") (pintype "power_in"))
      (node (ref "L3") (pin "1") (pinfunction "1_1") (pintype "passive"))
      (node (ref "U$1") (pin "1") (pinfunction "P$1_1") (pintype "bidirectional"))
      (node (ref "U3") (pin "4") (pinfunction "V+_4") (pintype "power_in"))
    )
    (net (code "105") (name "VEE") (class "Default")
      (node (ref "C10") (pin "2") (pinfunction "2_2") (pintype "passive"))
      (node (ref "C25") (pin "2") (pinfunction "2_2") (pintype "passive"))
      (node (ref "C37") (pin "2") (pinfunction "2_2") (pintype "passive"))
      (node (ref "C9") (pin "2") (pinfunction "2_2") (pintype "passive"))
      (node (ref "IC14") (pin "11") (pinfunction "V-_11") (pintype "power_in"))
      (node (ref "L4") (pin "1") (pinfunction "1_1") (pintype "passive"))
      (node (ref "R1") (pin "1") (pinfunction "1_1") (pintype "passive"))
      (node (ref "U$1") (pin "2") (pinfunction "P$2_2") (pintype "bidirectional"))
      (node (ref "U3") (pin "11") (pinfunction "V-_11") (pintype "power_in"))
    )
    (net (code "106") (name "unconnected-(IC4A-X7-Pad4)") (class "Default")
      (node (ref "IC4") (pin "4") (pinfunction "X7_4") (pintype "bidirectional"))
    )
    (net (code "107") (name "unconnected-(IC5-OUT0-Pad5)") (class "Default")
      (node (ref "IC5") (pin "5") (pinfunction "OUT0_5") (pintype "bidirectional"))
    )
    (net (code "108") (name "unconnected-(IC5-OUT1-Pad6)") (class "Default")
      (node (ref "IC5") (pin "6") (pinfunction "OUT1_6") (pintype "bidirectional"))
    )
    (net (code "109") (name "unconnected-(IC5-OUT11-Pad16)") (class "Default")
      (node (ref "IC5") (pin "16") (pinfunction "OUT11_16") (pintype "bidirectional"))
    )
    (net (code "110") (name "unconnected-(IC5-OUT12-Pad17)") (class "Default")
      (node (ref "IC5") (pin "17") (pinfunction "OUT12_17") (pintype "bidirectional"))
    )
    (net (code "111") (name "unconnected-(IC5-OUT13-Pad18)") (class "Default")
      (node (ref "IC5") (pin "18") (pinfunction "OUT13_18") (pintype "bidirectional"))
    )
    (net (code "112") (name "unconnected-(IC5-OUT14-Pad19)") (class "Default")
      (node (ref "IC5") (pin "19") (pinfunction "OUT14_19") (pintype "bidirectional"))
    )
    (net (code "113") (name "unconnected-(IC5-OUT15-Pad20)") (class "Default")
      (node (ref "IC5") (pin "20") (pinfunction "OUT15_20") (pintype "bidirectional"))
    )
    (net (code "114") (name "unconnected-(IC5-SOUT-Pad22)") (class "Default")
      (node (ref "IC5") (pin "22") (pinfunction "SOUT_22") (pintype "bidirectional"))
    )
    (net (code "115") (name "unconnected-(J7-2-PadP2)") (class "Default")
      (node (ref "J7") (pin "P2") (pinfunction "2_P2") (pintype "passive"))
    )
    (net (code "116") (name "unconnected-(J8-2-PadP2)") (class "Default")
      (node (ref "J8") (pin "P2") (pinfunction "2_P2") (pintype "passive"))
    )
    (net (code "117") (name "unconnected-(J9-2-PadP2)") (class "Default")
      (node (ref "J9") (pin "P2") (pinfunction "2_P2") (pintype "passive"))
    )
    (net (code "118") (name "unconnected-(J10-2-PadP2)") (class "Default")
      (node (ref "J10") (pin "P2") (pinfunction "2_P2") (pintype "passive"))
    )
    (net (code "119") (name "unconnected-(J11-2-PadP2)") (class "Default")
      (node (ref "J11") (pin "P2") (pinfunction "2_P2") (pintype "passive"))
    )
    (net (code "120") (name "unconnected-(J12-2-PadP2)") (class "Default")
      (node (ref "J12") (pin "P2") (pinfunction "2_P2") (pintype "passive"))
    )
  )
)
